# photoduino_shield_v_1_0.net
KiCad netlist of a schematic drawn in EAGLE
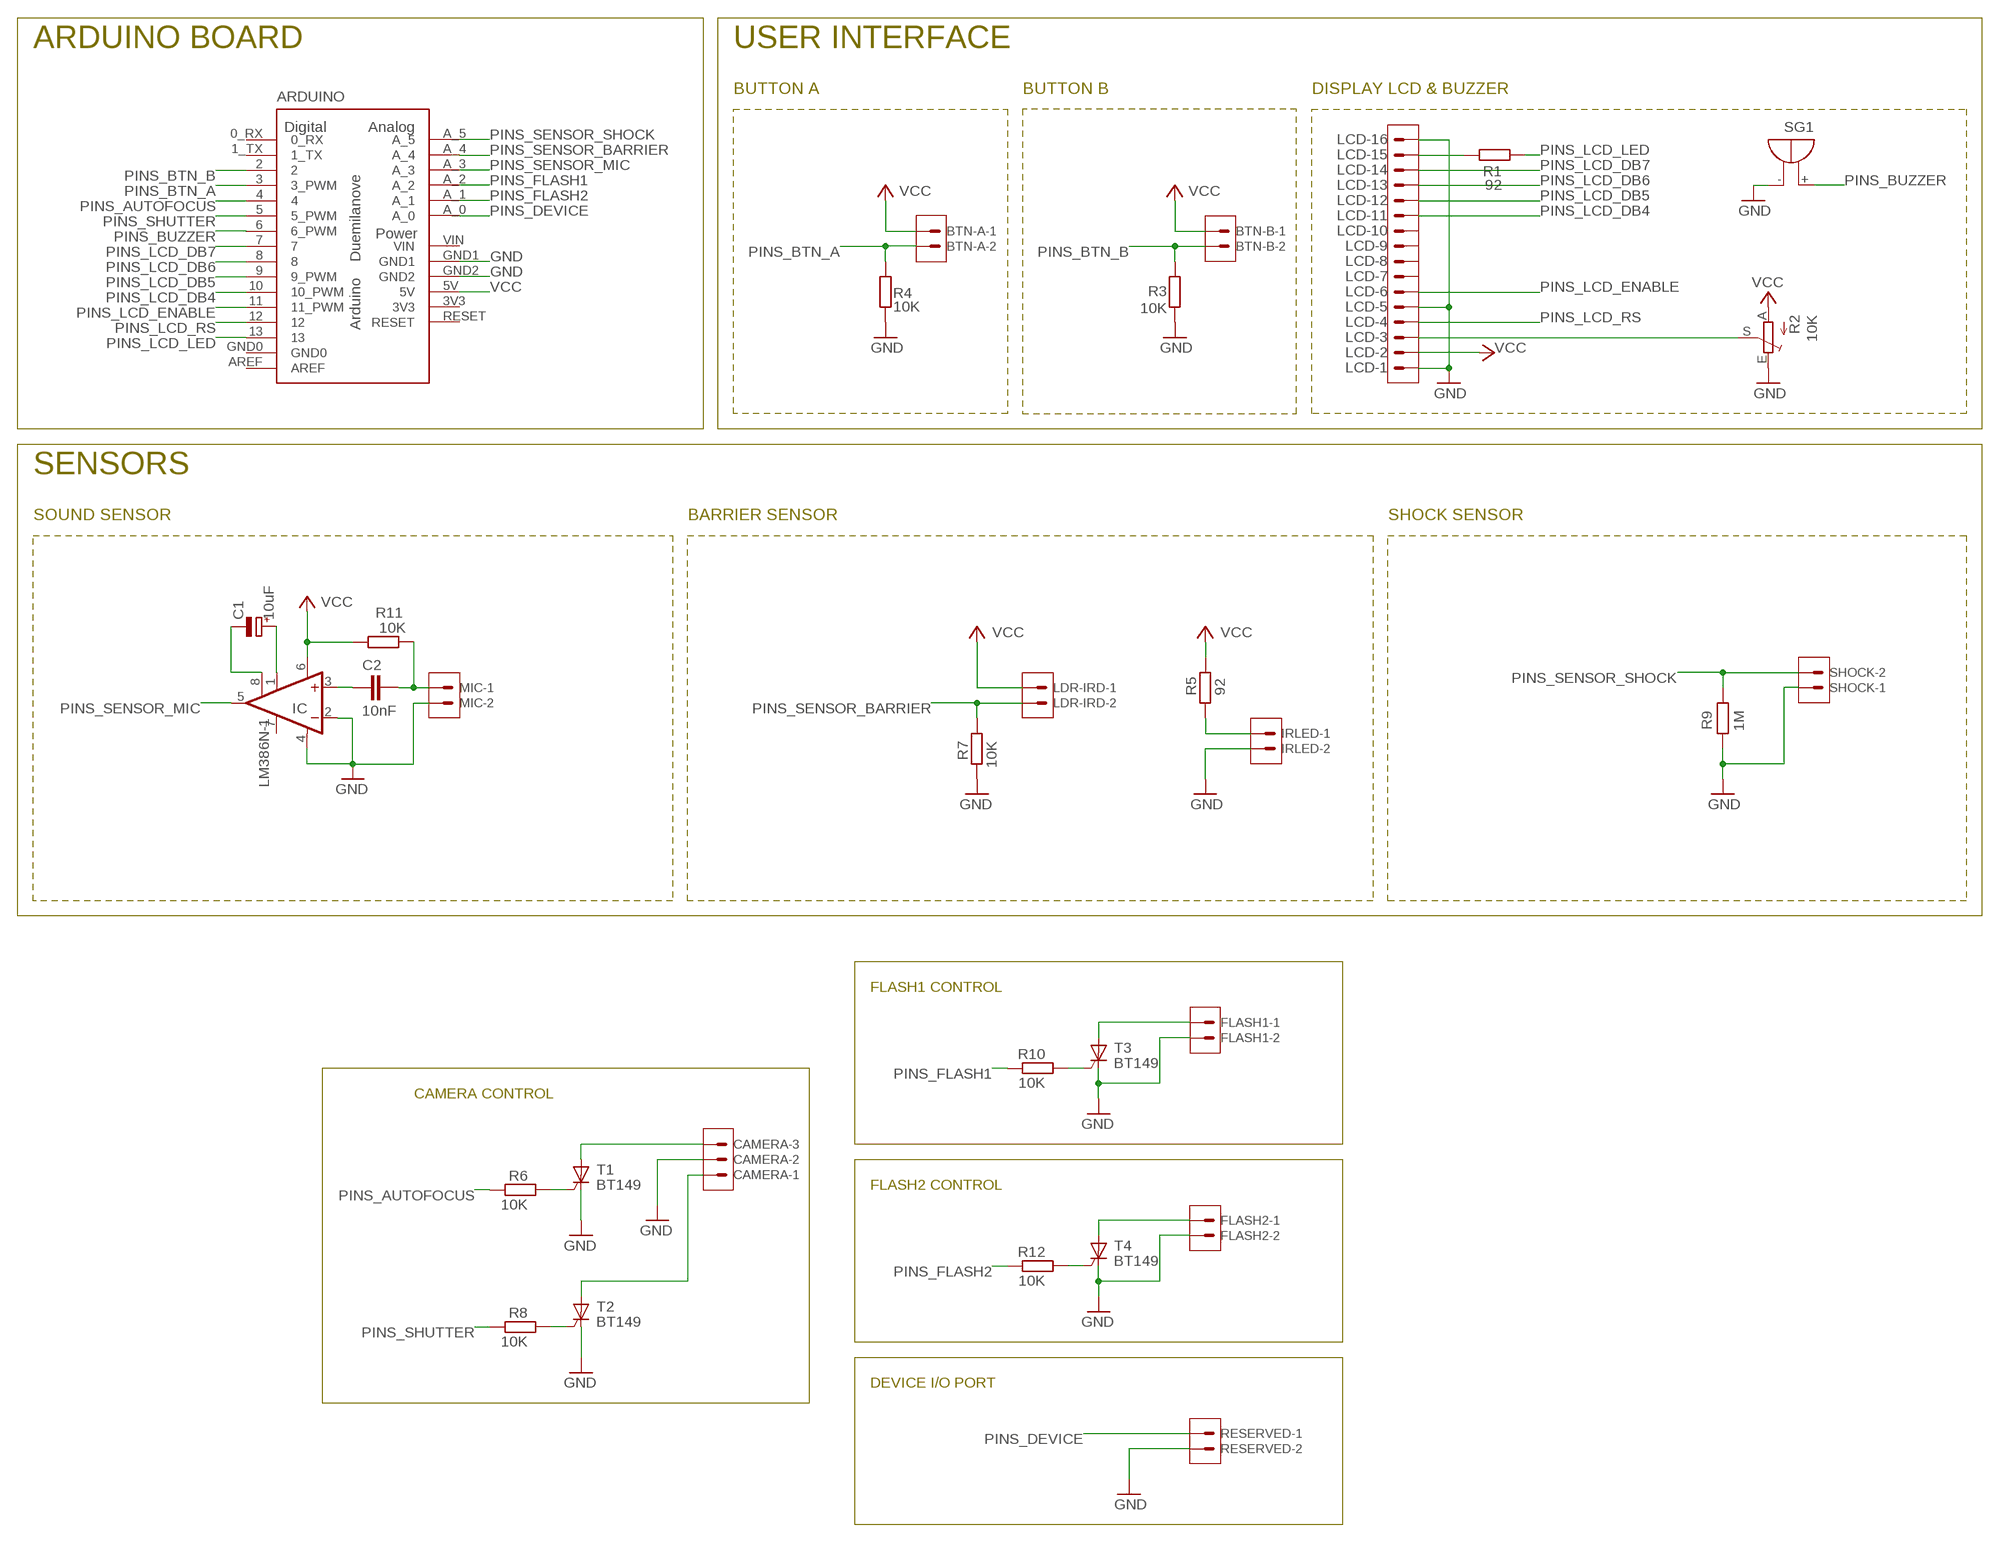
[diagram p0: schematic, sheet 1]

(export (version "E")
  (design (tool "Eeschema 10.0.6"))
  (components
    (comp (ref "ARDUINO")
      (value "ARDUINO-USBNO-OUTLINE-NO-TEXT-OCTAGONAL")
      (footprint "eagle-import:NO-OUTLINE-OCTAGONAL-NOTEXT")
      (libsource (lib "eagle-import") (part "ARDUINO-USBNO-OUTLINE-NO-TEXT-OCTAGONAL"))
    )
    (comp (ref "BTN-A")
      (value "22-27-2021-02")
      (footprint "eagle-import:6410-02")
      (libsource (lib "eagle-import") (part "22-?-0227-2021"))
    )
    (comp (ref "BTN-B")
      (value "22-27-2021-02")
      (footprint "eagle-import:6410-02")
      (libsource (lib "eagle-import") (part "22-?-0227-2021"))
    )
    (comp (ref "C1")
      (value "10uF")
      (footprint "eagle-import:E2,5-6")
      (libsource (lib "eagle-import") (part "CPOL-EUE2.5-6"))
    )
    (comp (ref "C2")
      (value "10nF")
      (footprint "eagle-import:C050-025X075")
      (libsource (lib "eagle-import") (part "C-EU050-025X075"))
    )
    (comp (ref "CAMERA")
      (value "22-27-2031-03")
      (footprint "eagle-import:6410-03")
      (libsource (lib "eagle-import") (part "22-?-0327-2031"))
    )
    (comp (ref "FLASH1")
      (value "22-27-2021-02")
      (footprint "eagle-import:6410-02")
      (libsource (lib "eagle-import") (part "22-?-0227-2021"))
    )
    (comp (ref "FLASH2")
      (value "22-27-2021-02")
      (footprint "eagle-import:6410-02")
      (libsource (lib "eagle-import") (part "22-?-0227-2021"))
    )
    (comp (ref "IC")
      (value "LM386N-1")
      (footprint "eagle-import:DIL08")
      (libsource (lib "eagle-import") (part "LM386?-N1"))
    )
    (comp (ref "IRLED")
      (value "22-27-2021-02")
      (footprint "eagle-import:6410-02")
      (libsource (lib "eagle-import") (part "22-?-0227-2021"))
    )
    (comp (ref "LCD")
      (value "HD44780")
      (footprint "eagle-import:ML16")
      (libsource (lib "eagle-import") (part "ML16E"))
    )
    (comp (ref "LDR-IRD")
      (value "22-27-2021-02")
      (footprint "eagle-import:6410-02")
      (libsource (lib "eagle-import") (part "22-?-0227-2021"))
    )
    (comp (ref "MIC")
      (value "22-27-2021-02")
      (footprint "eagle-import:6410-02")
      (libsource (lib "eagle-import") (part "22-?-0227-2021"))
    )
    (comp (ref "R1")
      (value "92")
      (footprint "eagle-import:0207_10")
      (libsource (lib "eagle-import") (part "R-EU_0207/10"))
    )
    (comp (ref "R2")
      (value "10K")
      (footprint "eagle-import:RJ9W")
      (libsource (lib "eagle-import") (part "TRIM_EU-RJ9W"))
    )
    (comp (ref "R3")
      (value "10K")
      (footprint "eagle-import:0207_7")
      (libsource (lib "eagle-import") (part "R-EU_0207/7"))
    )
    (comp (ref "R4")
      (value "10K")
      (footprint "eagle-import:0207_7")
      (libsource (lib "eagle-import") (part "R-EU_0207/7"))
    )
    (comp (ref "R5")
      (value "92")
      (footprint "eagle-import:0207_7")
      (libsource (lib "eagle-import") (part "R-EU_0207/7"))
    )
    (comp (ref "R6")
      (value "10K")
      (footprint "eagle-import:0309V")
      (libsource (lib "eagle-import") (part "R-EU_0309/V"))
    )
    (comp (ref "R7")
      (value "10K")
      (footprint "eagle-import:0207_7")
      (libsource (lib "eagle-import") (part "R-EU_0207/7"))
    )
    (comp (ref "R8")
      (value "10K")
      (footprint "eagle-import:0309V")
      (libsource (lib "eagle-import") (part "R-EU_0309/V"))
    )
    (comp (ref "R9")
      (value "1M")
      (footprint "eagle-import:0309V")
      (libsource (lib "eagle-import") (part "R-EU_0309/V"))
    )
    (comp (ref "R10")
      (value "10K")
      (footprint "eagle-import:0309V")
      (libsource (lib "eagle-import") (part "R-EU_0309/V"))
    )
    (comp (ref "R11")
      (value "10K")
      (footprint "eagle-import:0207_7")
      (libsource (lib "eagle-import") (part "R-EU_0207/7"))
    )
    (comp (ref "R12")
      (value "10K")
      (footprint "eagle-import:0309V")
      (libsource (lib "eagle-import") (part "R-EU_0309/V"))
    )
    (comp (ref "RESERVED")
      (value "22-27-2021-02")
      (footprint "eagle-import:6410-02")
      (libsource (lib "eagle-import") (part "22-?-0227-2021"))
    )
    (comp (ref "SG1")
      (value "F/TMB")
      (footprint "eagle-import:F_TMB")
      (libsource (lib "eagle-import") (part "F/TMB"))
    )
    (comp (ref "SHOCK")
      (value "22-27-2021-02")
      (footprint "eagle-import:6410-02")
      (libsource (lib "eagle-import") (part "22-?-0227-2021"))
    )
    (comp (ref "T1")
      (value "BT149")
      (footprint "eagle-import:TO92-4")
      (libsource (lib "eagle-import") (part "BT149"))
    )
    (comp (ref "T2")
      (value "BT149")
      (footprint "eagle-import:TO92-4")
      (libsource (lib "eagle-import") (part "BT149"))
    )
    (comp (ref "T3")
      (value "BT149")
      (footprint "eagle-import:TO92-4")
      (libsource (lib "eagle-import") (part "BT149"))
    )
    (comp (ref "T4")
      (value "BT149")
      (footprint "eagle-import:TO92-4")
      (libsource (lib "eagle-import") (part "BT149"))
    )
  )
  (nets
    (net (code "1") (name "/3V3") (class "Default")
      (node (ref "ARDUINO") (pin "3V3") (pinfunction "3V3_3V3") (pintype "power_in"))
    )
    (net (code "2") (name "/GND0") (class "Default")
      (node (ref "ARDUINO") (pin "GND0") (pinfunction "GND0_GND0") (pintype "power_in"))
    )
    (net (code "3") (name "/PINS_AUTOFOCUS") (class "Default")
      (node (ref "ARDUINO") (pin "4") (pinfunction "4_4") (pintype "bidirectional"))
      (node (ref "R6") (pin "2") (pinfunction "2_2") (pintype "passive"))
    )
    (net (code "4") (name "/PINS_BTN_A") (class "Default")
      (node (ref "ARDUINO") (pin "3") (pinfunction "3_PWM_3") (pintype "bidirectional"))
      (node (ref "BTN-A") (pin "2") (pinfunction "S_2") (pintype "passive"))
      (node (ref "R4") (pin "2") (pinfunction "2_2") (pintype "passive"))
    )
    (net (code "5") (name "/PINS_BTN_B") (class "Default")
      (node (ref "ARDUINO") (pin "2") (pinfunction "2_2") (pintype "bidirectional"))
      (node (ref "BTN-B") (pin "2") (pinfunction "S_2") (pintype "passive"))
      (node (ref "R3") (pin "1") (pinfunction "1_1") (pintype "passive"))
    )
    (net (code "6") (name "/PINS_BUZZER") (class "Default")
      (node (ref "ARDUINO") (pin "6") (pinfunction "6_PWM_6") (pintype "bidirectional"))
      (node (ref "SG1") (pin "+") (pinfunction "+_+") (pintype "passive"))
    )
    (net (code "7") (name "/PINS_DEVICE") (class "Default")
      (node (ref "ARDUINO") (pin "A_0") (pinfunction "A_0_A_0") (pintype "input"))
      (node (ref "RESERVED") (pin "1") (pinfunction "S_1") (pintype "passive"))
    )
    (net (code "8") (name "/PINS_FLASH1") (class "Default")
      (node (ref "ARDUINO") (pin "A_2") (pinfunction "A_2_A_2") (pintype "input"))
      (node (ref "R10") (pin "2") (pinfunction "2_2") (pintype "passive"))
    )
    (net (code "9") (name "/PINS_FLASH2") (class "Default")
      (node (ref "ARDUINO") (pin "A_1") (pinfunction "A_1_A_1") (pintype "input"))
      (node (ref "R12") (pin "2") (pinfunction "2_2") (pintype "passive"))
    )
    (net (code "10") (name "/PINS_LCD_DB4") (class "Default")
      (node (ref "ARDUINO") (pin "10") (pinfunction "10_PWM_10") (pintype "bidirectional"))
      (node (ref "LCD") (pin "11") (pinfunction "S_11") (pintype "passive"))
    )
    (net (code "11") (name "/PINS_LCD_DB5") (class "Default")
      (node (ref "ARDUINO") (pin "9") (pinfunction "9_PWM_9") (pintype "bidirectional"))
      (node (ref "LCD") (pin "12") (pinfunction "S_12") (pintype "passive"))
    )
    (net (code "12") (name "/PINS_LCD_DB6") (class "Default")
      (node (ref "ARDUINO") (pin "8") (pinfunction "8_8") (pintype "bidirectional"))
      (node (ref "LCD") (pin "13") (pinfunction "S_13") (pintype "passive"))
    )
    (net (code "13") (name "/PINS_LCD_DB7") (class "Default")
      (node (ref "ARDUINO") (pin "7") (pinfunction "7_7") (pintype "bidirectional"))
      (node (ref "LCD") (pin "14") (pinfunction "S_14") (pintype "passive"))
    )
    (net (code "14") (name "/PINS_LCD_ENABLE") (class "Default")
      (node (ref "ARDUINO") (pin "11") (pinfunction "11_PWM_11") (pintype "bidirectional"))
      (node (ref "LCD") (pin "6") (pinfunction "S_6") (pintype "passive"))
    )
    (net (code "15") (name "/PINS_LCD_LED") (class "Default")
      (node (ref "ARDUINO") (pin "13") (pinfunction "13_13") (pintype "bidirectional"))
      (node (ref "R1") (pin "1") (pinfunction "1_1") (pintype "passive"))
    )
    (net (code "16") (name "/PINS_LCD_RS") (class "Default")
      (node (ref "ARDUINO") (pin "12") (pinfunction "12_12") (pintype "bidirectional"))
      (node (ref "LCD") (pin "4") (pinfunction "S_4") (pintype "passive"))
    )
    (net (code "17") (name "/PINS_SENSOR_BARRIER") (class "Default")
      (node (ref "ARDUINO") (pin "A_4") (pinfunction "A_4_A_4") (pintype "input"))
      (node (ref "LDR-IRD") (pin "2") (pinfunction "S_2") (pintype "passive"))
      (node (ref "R7") (pin "1") (pinfunction "1_1") (pintype "passive"))
    )
    (net (code "18") (name "/PINS_SENSOR_MIC") (class "Default")
      (node (ref "ARDUINO") (pin "A_3") (pinfunction "A_3_A_3") (pintype "input"))
      (node (ref "IC") (pin "5") (pinfunction "OUT_5") (pintype "output"))
    )
    (net (code "19") (name "/PINS_SENSOR_SHOCK") (class "Default")
      (node (ref "ARDUINO") (pin "A_5") (pinfunction "A_5_A_5") (pintype "input"))
      (node (ref "R9") (pin "2") (pinfunction "2_2") (pintype "passive"))
      (node (ref "SHOCK") (pin "2") (pinfunction "S_2") (pintype "passive"))
    )
    (net (code "20") (name "/PINS_SHUTTER") (class "Default")
      (node (ref "ARDUINO") (pin "5") (pinfunction "5_PWM_5") (pintype "bidirectional"))
      (node (ref "R8") (pin "2") (pinfunction "2_2") (pintype "passive"))
    )
    (net (code "21") (name "/VIN") (class "Default")
      (node (ref "ARDUINO") (pin "VIN") (pinfunction "VIN_VIN") (pintype "power_in"))
    )
    (net (code "22") (name "GND") (class "Default")
      (node (ref "ARDUINO") (pin "GND1") (pinfunction "GND1_GND1") (pintype "power_in"))
      (node (ref "ARDUINO") (pin "GND2") (pinfunction "GND2_GND2") (pintype "power_in"))
      (node (ref "CAMERA") (pin "2") (pinfunction "S_2") (pintype "passive"))
      (node (ref "FLASH1") (pin "2") (pinfunction "S_2") (pintype "passive"))
      (node (ref "FLASH2") (pin "2") (pinfunction "S_2") (pintype "passive"))
      (node (ref "IC") (pin "2") (pinfunction "-IN_2") (pintype "input"))
      (node (ref "IC") (pin "4") (pinfunction "GND_4") (pintype "power_in"))
      (node (ref "IRLED") (pin "2") (pinfunction "S_2") (pintype "passive"))
      (node (ref "LCD") (pin "1") (pinfunction "S_1") (pintype "passive"))
      (node (ref "LCD") (pin "16") (pinfunction "S_16") (pintype "passive"))
      (node (ref "LCD") (pin "5") (pinfunction "S_5") (pintype "passive"))
      (node (ref "MIC") (pin "2") (pinfunction "S_2") (pintype "passive"))
      (node (ref "R2") (pin "E") (pinfunction "E_E") (pintype "passive"))
      (node (ref "R3") (pin "2") (pinfunction "2_2") (pintype "passive"))
      (node (ref "R4") (pin "1") (pinfunction "1_1") (pintype "passive"))
      (node (ref "R7") (pin "2") (pinfunction "2_2") (pintype "passive"))
      (node (ref "R9") (pin "1") (pinfunction "1_1") (pintype "passive"))
      (node (ref "RESERVED") (pin "2") (pinfunction "S_2") (pintype "passive"))
      (node (ref "SG1") (pin "-") (pinfunction "-_-") (pintype "passive"))
      (node (ref "SHOCK") (pin "1") (pinfunction "S_1") (pintype "passive"))
      (node (ref "T1") (pin "C") (pinfunction "C_C") (pintype "passive"))
      (node (ref "T2") (pin "C") (pinfunction "C_C") (pintype "passive"))
      (node (ref "T3") (pin "C") (pinfunction "C_C") (pintype "passive"))
      (node (ref "T4") (pin "C") (pinfunction "C_C") (pintype "passive"))
    )
    (net (code "23") (name "Net-(C1-Pad+)") (class "Default")
      (node (ref "C1") (pin "+") (pinfunction "+_+") (pintype "passive"))
      (node (ref "IC") (pin "1") (pinfunction "GAIN_1") (pintype "passive"))
    )
    (net (code "24") (name "Net-(C1-Pad-)") (class "Default")
      (node (ref "C1") (pin "-") (pinfunction "-_-") (pintype "passive"))
      (node (ref "IC") (pin "8") (pinfunction "GAIN_8") (pintype "passive"))
    )
    (net (code "25") (name "Net-(CAMERAA-S)") (class "Default")
      (node (ref "CAMERA") (pin "1") (pinfunction "S_1") (pintype "passive"))
      (node (ref "T2") (pin "A") (pinfunction "A_A") (pintype "passive"))
    )
    (net (code "26") (name "Net-(CAMERAC-S)") (class "Default")
      (node (ref "CAMERA") (pin "3") (pinfunction "S_3") (pintype "passive"))
      (node (ref "T1") (pin "A") (pinfunction "A_A") (pintype "passive"))
    )
    (net (code "27") (name "Net-(FLASH1A-S)") (class "Default")
      (node (ref "FLASH1") (pin "1") (pinfunction "S_1") (pintype "passive"))
      (node (ref "T3") (pin "A") (pinfunction "A_A") (pintype "passive"))
    )
    (net (code "28") (name "Net-(FLASH2A-S)") (class "Default")
      (node (ref "FLASH2") (pin "1") (pinfunction "S_1") (pintype "passive"))
      (node (ref "T4") (pin "A") (pinfunction "A_A") (pintype "passive"))
    )
    (net (code "29") (name "Net-(IC-+IN)") (class "Default")
      (node (ref "C2") (pin "1") (pinfunction "1_1") (pintype "passive"))
      (node (ref "IC") (pin "3") (pinfunction "+IN_3") (pintype "input"))
    )
    (net (code "30") (name "Net-(IRLEDA-S)") (class "Default")
      (node (ref "IRLED") (pin "1") (pinfunction "S_1") (pintype "passive"))
      (node (ref "R5") (pin "1") (pinfunction "1_1") (pintype "passive"))
    )
    (net (code "31") (name "Net-(LCDG-S)") (class "Default")
      (node (ref "LCD") (pin "15") (pinfunction "S_15") (pintype "passive"))
      (node (ref "R1") (pin "2") (pinfunction "2_2") (pintype "passive"))
    )
    (net (code "32") (name "Net-(LCDJ-S)") (class "Default")
      (node (ref "LCD") (pin "3") (pinfunction "S_3") (pintype "passive"))
      (node (ref "R2") (pin "S") (pinfunction "S_S") (pintype "passive"))
    )
    (net (code "33") (name "Net-(MICA-S)") (class "Default")
      (node (ref "C2") (pin "2") (pinfunction "2_2") (pintype "passive"))
      (node (ref "MIC") (pin "1") (pinfunction "S_1") (pintype "passive"))
      (node (ref "R11") (pin "1") (pinfunction "1_1") (pintype "passive"))
    )
    (net (code "34") (name "Net-(R6-Pad1)") (class "Default")
      (node (ref "R6") (pin "1") (pinfunction "1_1") (pintype "passive"))
      (node (ref "T1") (pin "G") (pinfunction "G_G") (pintype "passive"))
    )
    (net (code "35") (name "Net-(R8-Pad1)") (class "Default")
      (node (ref "R8") (pin "1") (pinfunction "1_1") (pintype "passive"))
      (node (ref "T2") (pin "G") (pinfunction "G_G") (pintype "passive"))
    )
    (net (code "36") (name "Net-(R10-Pad1)") (class "Default")
      (node (ref "R10") (pin "1") (pinfunction "1_1") (pintype "passive"))
      (node (ref "T3") (pin "G") (pinfunction "G_G") (pintype "passive"))
    )
    (net (code "37") (name "Net-(R12-Pad1)") (class "Default")
      (node (ref "R12") (pin "1") (pinfunction "1_1") (pintype "passive"))
      (node (ref "T4") (pin "G") (pinfunction "G_G") (pintype "passive"))
    )
    (net (code "38") (name "VCC") (class "Default")
      (node (ref "ARDUINO") (pin "5V") (pinfunction "5V_5V") (pintype "power_in"))
      (node (ref "BTN-A") (pin "1") (pinfunction "S_1") (pintype "passive"))
      (node (ref "BTN-B") (pin "1") (pinfunction "S_1") (pintype "passive"))
      (node (ref "IC") (pin "6") (pinfunction "VS_6") (pintype "power_in"))
      (node (ref "LCD") (pin "2") (pinfunction "S_2") (pintype "passive"))
      (node (ref "LDR-IRD") (pin "1") (pinfunction "S_1") (pintype "passive"))
      (node (ref "R11") (pin "2") (pinfunction "2_2") (pintype "passive"))
      (node (ref "R2") (pin "A") (pinfunction "A_A") (pintype "passive"))
      (node (ref "R5") (pin "2") (pinfunction "2_2") (pintype "passive"))
    )
    (net (code "39") (name "unconnected-(ARDUINO-Pad0_RX)") (class "Default")
      (node (ref "ARDUINO") (pin "0_RX") (pinfunction "0_RX_0_RX") (pintype "bidirectional"))
    )
    (net (code "40") (name "unconnected-(ARDUINO-Pad1_TX)") (class "Default")
      (node (ref "ARDUINO") (pin "1_TX") (pinfunction "1_TX_1_TX") (pintype "bidirectional"))
    )
    (net (code "41") (name "unconnected-(ARDUINO-PadAREF)") (class "Default")
      (node (ref "ARDUINO") (pin "AREF") (pinfunction "AREF_AREF") (pintype "bidirectional"))
    )
    (net (code "42") (name "unconnected-(ARDUINO-PadRESET)") (class "Default")
      (node (ref "ARDUINO") (pin "RESET") (pinfunction "RESET_RESET") (pintype "input"))
    )
    (net (code "43") (name "unconnected-(IC-BYPASS-Pad7)") (class "Default")
      (node (ref "IC") (pin "7") (pinfunction "BYPASS_7") (pintype "passive"))
    )
    (net (code "44") (name "unconnected-(LCDB-S-Pad10)") (class "Default")
      (node (ref "LCD") (pin "10") (pinfunction "S_10") (pintype "passive"))
    )
    (net (code "45") (name "unconnected-(LCDN-S-Pad7)") (class "Default")
      (node (ref "LCD") (pin "7") (pinfunction "S_7") (pintype "passive"))
    )
    (net (code "46") (name "unconnected-(LCDO-S-Pad8)") (class "Default")
      (node (ref "LCD") (pin "8") (pinfunction "S_8") (pintype "passive"))
    )
    (net (code "47") (name "unconnected-(LCDP-S-Pad9)") (class "Default")
      (node (ref "LCD") (pin "9") (pinfunction "S_9") (pintype "passive"))
    )
  )
)
